# breakout_proto.net
KiCad netlist of a schematic drawn in EAGLE
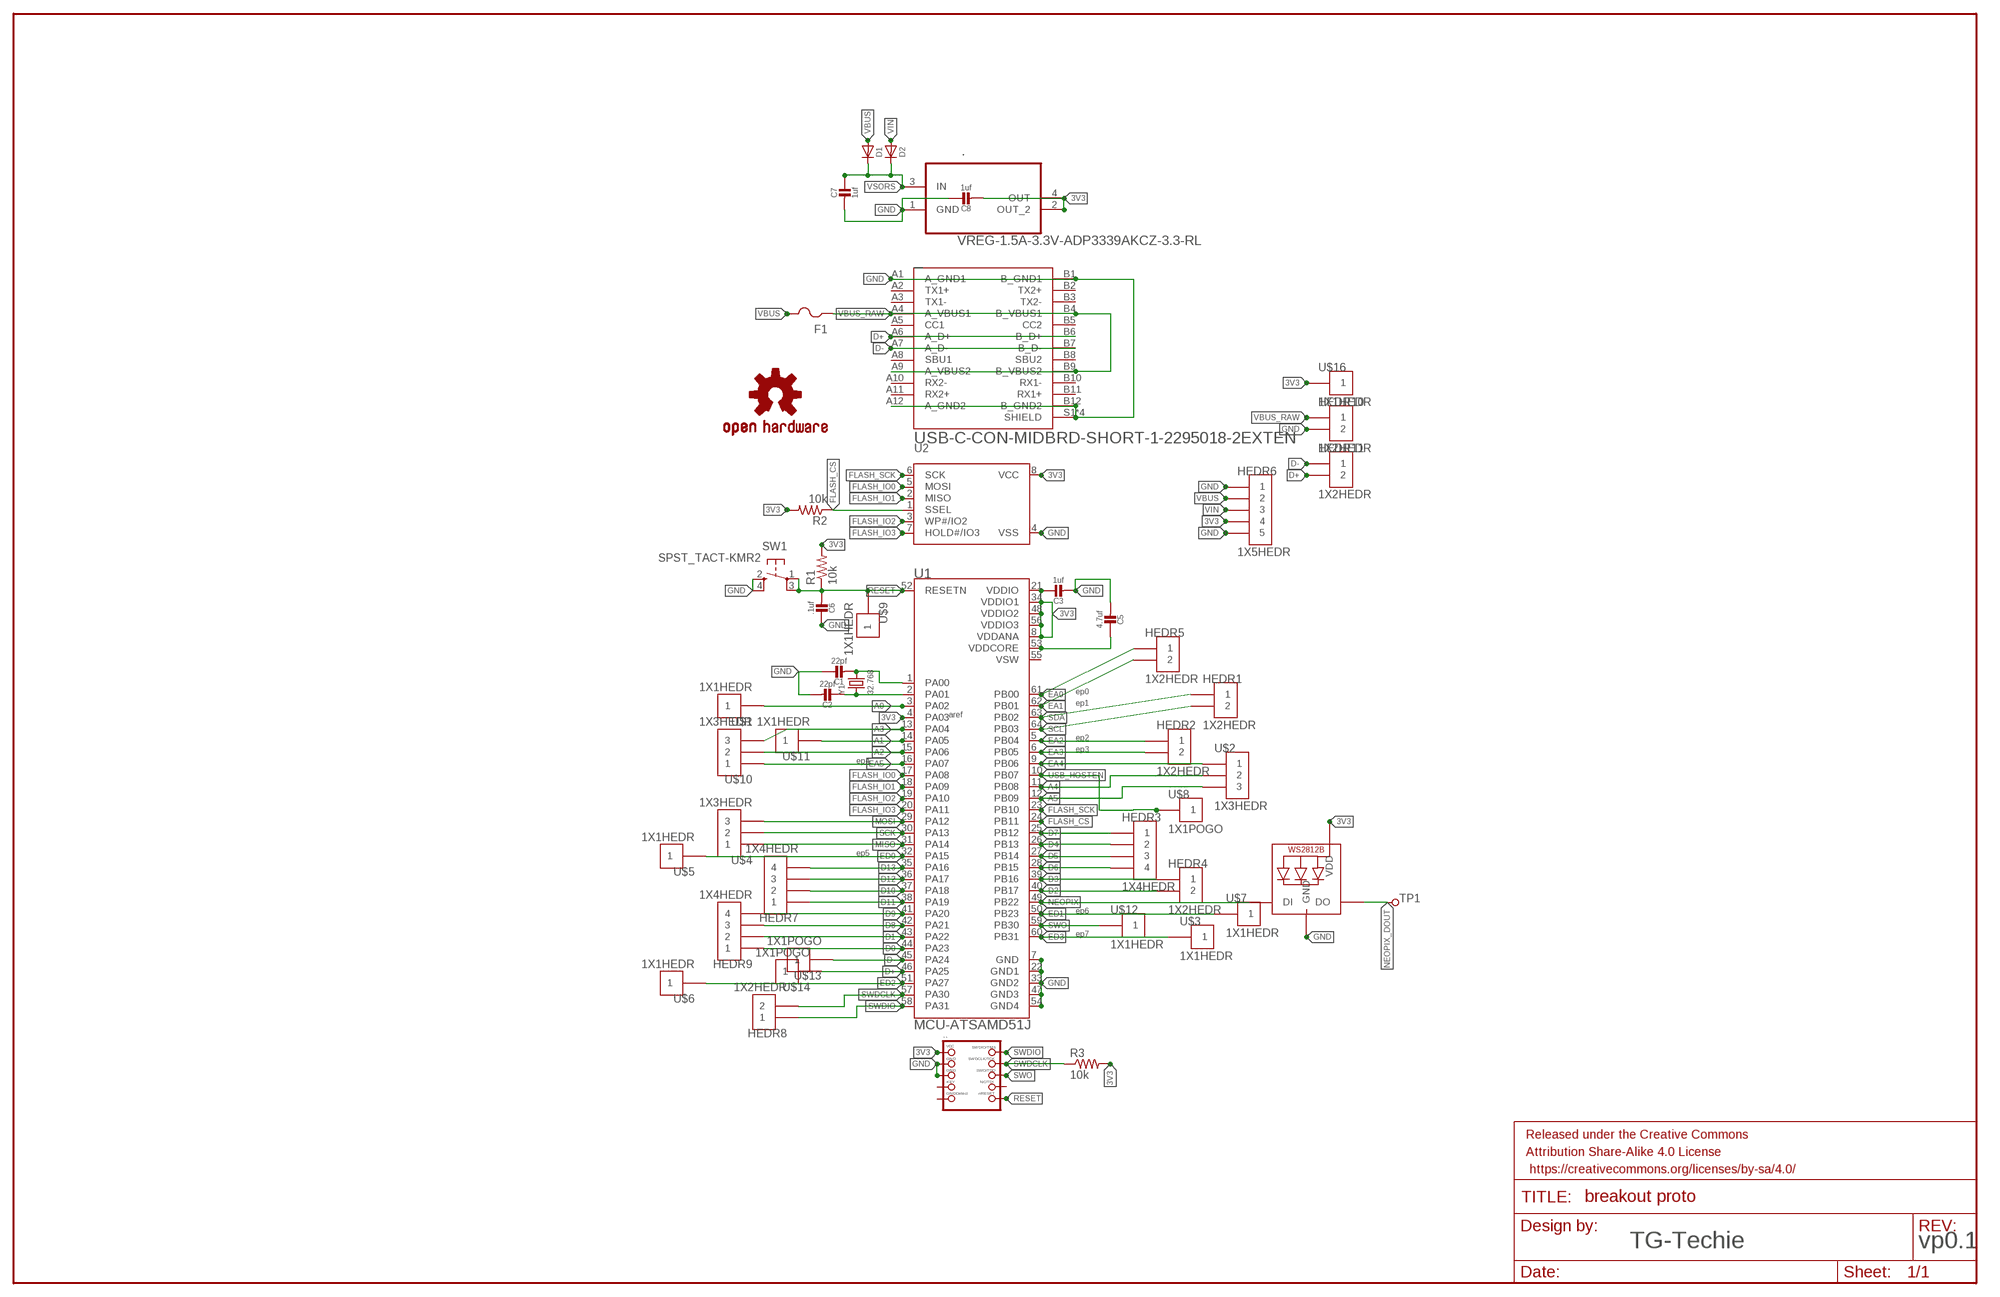
[diagram p0: schematic, sheet 1]

(export (version "E")
  (design (tool "Eeschema 10.0.6"))
  (components
    (comp (ref ".")
      (value "VREG-1.5A-3.3V-ADP3339AKCZ-3.3-RL")
      (footprint "eagle-import:SOT230P700X180-4N")
      (fields (field (name "MF") "Analog Devices") (field (name "MP") "ADP3339AKCZ-3.3-RL"))
      (libsource (lib "eagle-import") (part "VREG-1.5A-3.3V-ADP3339AKCZ-3.3-RL"))
    )
    (comp (ref "..")
      (value "INTRFC-JTAG-CORTEXBOXPOSTS")
      (footprint "eagle-import:2X05_1.27MM_BOX_POSTS")
      (libsource (lib "eagle-import") (part "INTRFC-JTAG-CORTEXBOXPOSTS"))
    )
    (comp (ref "C1")
      (value "22pf")
      (footprint "eagle-import:MICROBUILDER__0805")
      (libsource (lib "eagle-import") (part "C-US__0805"))
    )
    (comp (ref "C2")
      (value "22pf")
      (footprint "eagle-import:MICROBUILDER__0805")
      (libsource (lib "eagle-import") (part "C-US__0805"))
    )
    (comp (ref "C3")
      (value "1uf")
      (footprint "eagle-import:MICROBUILDER__0805")
      (libsource (lib "eagle-import") (part "C-US__0805"))
    )
    (comp (ref "C5")
      (value "4.7uf")
      (footprint "eagle-import:MICROBUILDER__0805")
      (libsource (lib "eagle-import") (part "C-US__0805"))
    )
    (comp (ref "C6")
      (value ".1uf")
      (footprint "eagle-import:MICROBUILDER__0805")
      (libsource (lib "eagle-import") (part "C-US__0805"))
    )
    (comp (ref "C7")
      (value "1uf")
      (footprint "eagle-import:MICROBUILDER__0805")
      (libsource (lib "eagle-import") (part "C-US__0805"))
    )
    (comp (ref "C8")
      (value "1uf")
      (footprint "eagle-import:MICROBUILDER__0805")
      (libsource (lib "eagle-import") (part "C-US__0805"))
    )
    (comp (ref "D1")
      (value "DIODESOD-123")
      (footprint "eagle-import:SOD-123")
      (libsource (lib "eagle-import") (part "DIODESOD-123"))
    )
    (comp (ref "D2")
      (value "DIODESOD-123")
      (footprint "eagle-import:SOD-123")
      (libsource (lib "eagle-import") (part "DIODESOD-123"))
    )
    (comp (ref "F1")
      (value "PTCFUSE-1206")
      (footprint "eagle-import:R1206")
      (libsource (lib "eagle-import") (part "PTCFUSE-1206"))
    )
    (comp (ref "FRAME1")
      (value "FRAME-LEDGER")
      (footprint "eagle-import:CREATIVE_COMMONS")
      (libsource (lib "eagle-import") (part "FRAME-LEDGER"))
    )
    (comp (ref "HEDR1")
      (value "1X2HEDR")
      (footprint "eagle-import:1X2_HEDR")
      (libsource (lib "eagle-import") (part "1X2HEDR"))
    )
    (comp (ref "HEDR2")
      (value "1X2HEDR")
      (footprint "eagle-import:1X2_HEDR")
      (libsource (lib "eagle-import") (part "1X2HEDR"))
    )
    (comp (ref "HEDR3")
      (value "1X4HEDR")
      (footprint "eagle-import:1X4_HEDR")
      (libsource (lib "eagle-import") (part "1X4HEDR"))
    )
    (comp (ref "HEDR4")
      (value "1X2HEDR")
      (footprint "eagle-import:1X2_HEDR")
      (libsource (lib "eagle-import") (part "1X2HEDR"))
    )
    (comp (ref "HEDR5")
      (value "1X2HEDR")
      (footprint "eagle-import:1X2_HEDR")
      (libsource (lib "eagle-import") (part "1X2HEDR"))
    )
    (comp (ref "HEDR6")
      (value "1X5HEDR")
      (footprint "eagle-import:1X5_HEDR")
      (libsource (lib "eagle-import") (part "1X5HEDR"))
    )
    (comp (ref "HEDR7")
      (value "1X4HEDR")
      (footprint "eagle-import:1X4_HEDR")
      (libsource (lib "eagle-import") (part "1X4HEDR"))
    )
    (comp (ref "HEDR8")
      (value "1X2HEDR")
      (footprint "eagle-import:1X2_HEDR")
      (libsource (lib "eagle-import") (part "1X2HEDR"))
    )
    (comp (ref "HEDR9")
      (value "1X4HEDR")
      (footprint "eagle-import:1X4_HEDR")
      (libsource (lib "eagle-import") (part "1X4HEDR"))
    )
    (comp (ref "HEDR10")
      (value "1X2HEDR")
      (footprint "eagle-import:1X2_HEDR")
      (libsource (lib "eagle-import") (part "1X2HEDR"))
    )
    (comp (ref "HEDR11")
      (value "1X2HEDR")
      (footprint "eagle-import:1X2_HEDR")
      (libsource (lib "eagle-import") (part "1X2HEDR"))
    )
    (comp (ref "LED1")
      (value "LED-NEO-WS2812B3535")
      (footprint "eagle-import:LED3535")
      (libsource (lib "eagle-import") (part "LED-NEO-WS2812B3535"))
    )
    (comp (ref "LOGO1")
      (value "OSHW-LOGOMINI")
      (footprint "eagle-import:OSHW-LOGO-MINI")
      (libsource (lib "eagle-import") (part "OSHW-LOGOMINI"))
    )
    (comp (ref "R1")
      (value "10k")
      (footprint "eagle-import:R0805")
      (libsource (lib "eagle-import") (part "R-US_R0805"))
    )
    (comp (ref "R2")
      (value "10k")
      (footprint "eagle-import:R0805")
      (libsource (lib "eagle-import") (part "R-US_R0805"))
    )
    (comp (ref "R3")
      (value "10k")
      (footprint "eagle-import:R0805")
      (libsource (lib "eagle-import") (part "R-US_R0805"))
    )
    (comp (ref "SW1")
      (value "SPST_TACT-KMR2")
      (footprint "eagle-import:KMR2")
      (libsource (lib "eagle-import") (part "SPST_TACT-KMR2"))
    )
    (comp (ref "TP1")
      (value "TESTPOINT_1X1")
      (footprint "eagle-import:1X1_POGO")
      (libsource (lib "eagle-import") (part "TESTPOINT_1X1"))
    )
    (comp (ref "U$1")
      (value "1X1HEDR")
      (footprint "eagle-import:1X1_HEDR")
      (libsource (lib "eagle-import") (part "1X1HEDR"))
    )
    (comp (ref "U$2")
      (value "1X3HEDR")
      (footprint "eagle-import:1X3_HEDR")
      (libsource (lib "eagle-import") (part "1X3HEDR"))
    )
    (comp (ref "U$3")
      (value "1X1HEDR")
      (footprint "eagle-import:1X1_HEDR")
      (libsource (lib "eagle-import") (part "1X1HEDR"))
    )
    (comp (ref "U$4")
      (value "1X3HEDR")
      (footprint "eagle-import:1X3_HEDR")
      (libsource (lib "eagle-import") (part "1X3HEDR"))
    )
    (comp (ref "U$5")
      (value "1X1HEDR")
      (footprint "eagle-import:1X1_HEDR")
      (libsource (lib "eagle-import") (part "1X1HEDR"))
    )
    (comp (ref "U$6")
      (value "1X1HEDR")
      (footprint "eagle-import:1X1_HEDR")
      (libsource (lib "eagle-import") (part "1X1HEDR"))
    )
    (comp (ref "U$7")
      (value "1X1HEDR")
      (footprint "eagle-import:1X1_HEDR")
      (libsource (lib "eagle-import") (part "1X1HEDR"))
    )
    (comp (ref "U$8")
      (value "1X1POGO")
      (footprint "eagle-import:1X1_POGO")
      (libsource (lib "eagle-import") (part "1X1POGO"))
    )
    (comp (ref "U$9")
      (value "1X1HEDR")
      (footprint "eagle-import:1X1_HEDR")
      (libsource (lib "eagle-import") (part "1X1HEDR"))
    )
    (comp (ref "U$10")
      (value "1X3HEDR")
      (footprint "eagle-import:1X3_HEDR")
      (libsource (lib "eagle-import") (part "1X3HEDR"))
    )
    (comp (ref "U$11")
      (value "1X1HEDR")
      (footprint "eagle-import:1X1_HEDR")
      (libsource (lib "eagle-import") (part "1X1HEDR"))
    )
    (comp (ref "U$12")
      (value "1X1HEDR")
      (footprint "eagle-import:1X1_HEDR")
      (libsource (lib "eagle-import") (part "1X1HEDR"))
    )
    (comp (ref "U$13")
      (value "1X1POGO")
      (footprint "eagle-import:1X1_POGO")
      (libsource (lib "eagle-import") (part "1X1POGO"))
    )
    (comp (ref "U$14")
      (value "1X1POGO")
      (footprint "eagle-import:1X1_POGO")
      (libsource (lib "eagle-import") (part "1X1POGO"))
    )
    (comp (ref "U$16")
      (value "1X1HEDR")
      (footprint "eagle-import:1X1_HEDR")
      (libsource (lib "eagle-import") (part "1X1HEDR"))
    )
    (comp (ref "U1")
      (value "MCU-ATSAMD51J")
      (footprint "eagle-import:QFP50P1200X1200X120-64N")
      (fields (field (name "MF") "Microchip") (field (name "MP") "ATSAMD51J20A-AU"))
      (libsource (lib "eagle-import") (part "MCU-ATSAMD51J"))
    )
    (comp (ref "U2")
      (value "FLASH-SPI-SOIC8208MIL")
      (footprint "eagle-import:SOIC8_208MIL")
      (libsource (lib "eagle-import") (part "FLASH-SPI-SOIC8208MIL"))
    )
    (comp (ref "Y1")
      (value "32.768")
      (footprint "eagle-import:MICROBUILDER_CRYSTAL_4.9X1.8")
      (libsource (lib "eagle-import") (part "XTAL_ADA4.9X1.8"))
    )
    (comp (ref "_")
      (value "USB-C-CON-MIDBRD-SHORT-1-2295018-2EXTEN")
      (footprint "eagle-import:TE_1-2295018-2_EXTEN")
      (libsource (lib "eagle-import") (part "USB-C-CON-MIDBRD-SHORT-1-2295018-2EXTEN"))
    )
  )
  (nets
    (net (code "1") (name "/VSW") (class "Default")
      (node (ref "U1") (pin "55") (pinfunction "VSW_55") (pintype "power_in"))
    )
    (net (code "2") (name "3V3") (class "Default")
      (node (ref ".") (pin "2") (pinfunction "OUT_2_2") (pintype "output"))
      (node (ref ".") (pin "4") (pinfunction "OUT_4") (pintype "output"))
      (node (ref "..") (pin "1") (pinfunction "VCC_1") (pintype "power_in"))
      (node (ref "C3") (pin "1") (pinfunction "1_1") (pintype "passive"))
      (node (ref "C8") (pin "2") (pinfunction "2_2") (pintype "passive"))
      (node (ref "HEDR6") (pin "4") (pinfunction "4_4") (pintype "bidirectional"))
      (node (ref "LED1") (pin "2") (pinfunction "VDD_2") (pintype "power_in"))
      (node (ref "R1") (pin "2") (pinfunction "2_2") (pintype "passive"))
      (node (ref "R2") (pin "2") (pinfunction "2_2") (pintype "passive"))
      (node (ref "R3") (pin "2") (pinfunction "2_2") (pintype "passive"))
      (node (ref "U$16") (pin "1") (pinfunction "1_1") (pintype "bidirectional"))
      (node (ref "U1") (pin "21") (pinfunction "VDDIO_21") (pintype "power_in"))
      (node (ref "U1") (pin "34") (pinfunction "VDDIO1_34") (pintype "power_in"))
      (node (ref "U1") (pin "4") (pinfunction "PA03_4") (pintype "bidirectional"))
      (node (ref "U1") (pin "48") (pinfunction "VDDIO2_48") (pintype "power_in"))
      (node (ref "U1") (pin "56") (pinfunction "VDDIO3_56") (pintype "power_in"))
      (node (ref "U1") (pin "8") (pinfunction "VDDANA_8") (pintype "power_in"))
      (node (ref "U2") (pin "8") (pinfunction "VCC_8") (pintype "bidirectional"))
    )
    (net (code "3") (name "A0") (class "Default")
      (node (ref "U$1") (pin "1") (pinfunction "1_1") (pintype "bidirectional"))
      (node (ref "U1") (pin "3") (pinfunction "PA02_3") (pintype "bidirectional"))
    )
    (net (code "4") (name "A1") (class "Default")
      (node (ref "U$11") (pin "1") (pinfunction "1_1") (pintype "bidirectional"))
      (node (ref "U1") (pin "14") (pinfunction "PA05_14") (pintype "bidirectional"))
    )
    (net (code "5") (name "A2") (class "Default")
      (node (ref "U$10") (pin "2") (pinfunction "2_2") (pintype "bidirectional"))
      (node (ref "U1") (pin "15") (pinfunction "PA06_15") (pintype "bidirectional"))
    )
    (net (code "6") (name "A3") (class "Default")
      (node (ref "U$10") (pin "3") (pinfunction "3_3") (pintype "bidirectional"))
      (node (ref "U1") (pin "13") (pinfunction "PA04_13") (pintype "bidirectional"))
    )
    (net (code "7") (name "A4") (class "Default")
      (node (ref "U$2") (pin "2") (pinfunction "2_2") (pintype "bidirectional"))
      (node (ref "U1") (pin "11") (pinfunction "PB08_11") (pintype "bidirectional"))
    )
    (net (code "8") (name "A5") (class "Default")
      (node (ref "U$2") (pin "3") (pinfunction "3_3") (pintype "bidirectional"))
      (node (ref "U1") (pin "12") (pinfunction "PB09_12") (pintype "bidirectional"))
    )
    (net (code "9") (name "D+") (class "Default")
      (node (ref "HEDR11") (pin "2") (pinfunction "2_2") (pintype "bidirectional"))
      (node (ref "U$14") (pin "1") (pinfunction "1_1") (pintype "bidirectional"))
      (node (ref "U1") (pin "46") (pinfunction "PA25_46") (pintype "bidirectional"))
      (node (ref "_") (pin "A6") (pinfunction "A_D+_A6") (pintype "passive"))
      (node (ref "_") (pin "B6") (pinfunction "B_D+_B6") (pintype "passive"))
    )
    (net (code "10") (name "D-") (class "Default")
      (node (ref "HEDR11") (pin "1") (pinfunction "1_1") (pintype "bidirectional"))
      (node (ref "U$13") (pin "1") (pinfunction "1_1") (pintype "bidirectional"))
      (node (ref "U1") (pin "45") (pinfunction "PA24_45") (pintype "bidirectional"))
      (node (ref "_") (pin "A7") (pinfunction "A_D-_A7") (pintype "passive"))
      (node (ref "_") (pin "B7") (pinfunction "B_D-_B7") (pintype "passive"))
    )
    (net (code "11") (name "D0") (class "Default")
      (node (ref "HEDR9") (pin "1") (pinfunction "1_1") (pintype "bidirectional"))
      (node (ref "U1") (pin "44") (pinfunction "PA23_44") (pintype "bidirectional"))
    )
    (net (code "12") (name "D1") (class "Default")
      (node (ref "HEDR9") (pin "2") (pinfunction "2_2") (pintype "bidirectional"))
      (node (ref "U1") (pin "43") (pinfunction "PA22_43") (pintype "bidirectional"))
    )
    (net (code "13") (name "D2") (class "Default")
      (node (ref "HEDR4") (pin "2") (pinfunction "2_2") (pintype "bidirectional"))
      (node (ref "U1") (pin "40") (pinfunction "PB17_40") (pintype "bidirectional"))
    )
    (net (code "14") (name "D3") (class "Default")
      (node (ref "HEDR4") (pin "1") (pinfunction "1_1") (pintype "bidirectional"))
      (node (ref "U1") (pin "39") (pinfunction "PB16_39") (pintype "bidirectional"))
    )
    (net (code "15") (name "D4") (class "Default")
      (node (ref "HEDR3") (pin "2") (pinfunction "2_2") (pintype "bidirectional"))
      (node (ref "U1") (pin "26") (pinfunction "PB13_26") (pintype "bidirectional"))
    )
    (net (code "16") (name "D5") (class "Default")
      (node (ref "HEDR3") (pin "3") (pinfunction "3_3") (pintype "bidirectional"))
      (node (ref "U1") (pin "27") (pinfunction "PB14_27") (pintype "bidirectional"))
    )
    (net (code "17") (name "D6") (class "Default")
      (node (ref "HEDR3") (pin "4") (pinfunction "4_4") (pintype "bidirectional"))
      (node (ref "U1") (pin "28") (pinfunction "PB15_28") (pintype "bidirectional"))
    )
    (net (code "18") (name "D7") (class "Default")
      (node (ref "HEDR3") (pin "1") (pinfunction "1_1") (pintype "bidirectional"))
      (node (ref "U1") (pin "25") (pinfunction "PB12_25") (pintype "bidirectional"))
    )
    (net (code "19") (name "D8") (class "Default")
      (node (ref "HEDR9") (pin "3") (pinfunction "3_3") (pintype "bidirectional"))
      (node (ref "U1") (pin "42") (pinfunction "PA21_42") (pintype "bidirectional"))
    )
    (net (code "20") (name "D9") (class "Default")
      (node (ref "HEDR9") (pin "4") (pinfunction "4_4") (pintype "bidirectional"))
      (node (ref "U1") (pin "41") (pinfunction "PA20_41") (pintype "bidirectional"))
    )
    (net (code "21") (name "D10") (class "Default")
      (node (ref "HEDR7") (pin "2") (pinfunction "2_2") (pintype "bidirectional"))
      (node (ref "U1") (pin "37") (pinfunction "PA18_37") (pintype "bidirectional"))
    )
    (net (code "22") (name "D11") (class "Default")
      (node (ref "HEDR7") (pin "1") (pinfunction "1_1") (pintype "bidirectional"))
      (node (ref "U1") (pin "38") (pinfunction "PA19_38") (pintype "bidirectional"))
    )
    (net (code "23") (name "D12") (class "Default")
      (node (ref "HEDR7") (pin "3") (pinfunction "3_3") (pintype "bidirectional"))
      (node (ref "U1") (pin "36") (pinfunction "PA17_36") (pintype "bidirectional"))
    )
    (net (code "24") (name "D13") (class "Default")
      (node (ref "HEDR7") (pin "4") (pinfunction "4_4") (pintype "bidirectional"))
      (node (ref "U1") (pin "35") (pinfunction "PA16_35") (pintype "bidirectional"))
    )
    (net (code "25") (name "EA0") (class "Default")
      (node (ref "HEDR5") (pin "1") (pinfunction "1_1") (pintype "bidirectional"))
      (node (ref "U1") (pin "61") (pinfunction "PB00_61") (pintype "bidirectional"))
    )
    (net (code "26") (name "EA1") (class "Default")
      (node (ref "HEDR5") (pin "2") (pinfunction "2_2") (pintype "bidirectional"))
      (node (ref "U1") (pin "62") (pinfunction "PB01_62") (pintype "bidirectional"))
    )
    (net (code "27") (name "EA2") (class "Default")
      (node (ref "HEDR2") (pin "1") (pinfunction "1_1") (pintype "bidirectional"))
      (node (ref "U1") (pin "5") (pinfunction "PB04_5") (pintype "bidirectional"))
    )
    (net (code "28") (name "EA3") (class "Default")
      (node (ref "HEDR2") (pin "2") (pinfunction "2_2") (pintype "bidirectional"))
      (node (ref "U1") (pin "6") (pinfunction "PB05_6") (pintype "bidirectional"))
    )
    (net (code "29") (name "EA4") (class "Default")
      (node (ref "U$2") (pin "1") (pinfunction "1_1") (pintype "bidirectional"))
      (node (ref "U1") (pin "9") (pinfunction "PB06_9") (pintype "bidirectional"))
    )
    (net (code "30") (name "EA5") (class "Default")
      (node (ref "U$10") (pin "1") (pinfunction "1_1") (pintype "bidirectional"))
      (node (ref "U1") (pin "16") (pinfunction "PA07_16") (pintype "bidirectional"))
    )
    (net (code "31") (name "ED0") (class "Default")
      (node (ref "U$5") (pin "1") (pinfunction "1_1") (pintype "bidirectional"))
      (node (ref "U1") (pin "32") (pinfunction "PA15_32") (pintype "bidirectional"))
    )
    (net (code "32") (name "ED1") (class "Default")
      (node (ref "U$7") (pin "1") (pinfunction "1_1") (pintype "bidirectional"))
      (node (ref "U1") (pin "50") (pinfunction "PB23_50") (pintype "bidirectional"))
    )
    (net (code "33") (name "ED2") (class "Default")
      (node (ref "U$6") (pin "1") (pinfunction "1_1") (pintype "bidirectional"))
      (node (ref "U1") (pin "51") (pinfunction "PA27_51") (pintype "bidirectional"))
    )
    (net (code "34") (name "ED3") (class "Default")
      (node (ref "U$3") (pin "1") (pinfunction "1_1") (pintype "bidirectional"))
      (node (ref "U1") (pin "60") (pinfunction "PB31_60") (pintype "bidirectional"))
    )
    (net (code "35") (name "FLASH_CS") (class "Default")
      (node (ref "R2") (pin "1") (pinfunction "1_1") (pintype "passive"))
      (node (ref "U1") (pin "24") (pinfunction "PB11_24") (pintype "bidirectional"))
      (node (ref "U2") (pin "1") (pinfunction "SSEL_1") (pintype "bidirectional"))
    )
    (net (code "36") (name "FLASH_IO0") (class "Default")
      (node (ref "U1") (pin "17") (pinfunction "PA08_17") (pintype "bidirectional"))
      (node (ref "U2") (pin "5") (pinfunction "MOSI_5") (pintype "bidirectional"))
    )
    (net (code "37") (name "FLASH_IO1") (class "Default")
      (node (ref "U1") (pin "18") (pinfunction "PA09_18") (pintype "bidirectional"))
      (node (ref "U2") (pin "2") (pinfunction "MISO_2") (pintype "bidirectional"))
    )
    (net (code "38") (name "FLASH_IO2") (class "Default")
      (node (ref "U1") (pin "19") (pinfunction "PA10_19") (pintype "bidirectional"))
      (node (ref "U2") (pin "3") (pinfunction "WP#/IO2_3") (pintype "bidirectional"))
    )
    (net (code "39") (name "FLASH_IO3") (class "Default")
      (node (ref "U1") (pin "20") (pinfunction "PA11_20") (pintype "bidirectional"))
      (node (ref "U2") (pin "7") (pinfunction "HOLD#/IO3_7") (pintype "bidirectional"))
    )
    (net (code "40") (name "FLASH_SCK") (class "Default")
      (node (ref "U1") (pin "23") (pinfunction "PB10_23") (pintype "bidirectional"))
      (node (ref "U2") (pin "6") (pinfunction "SCK_6") (pintype "bidirectional"))
    )
    (net (code "41") (name "GND") (class "Default")
      (node (ref ".") (pin "1") (pinfunction "GND_1") (pintype "passive"))
      (node (ref "..") (pin "3") (pinfunction "GND_3") (pintype "power_in"))
      (node (ref "..") (pin "5") (pinfunction "GND_5") (pintype "power_in"))
      (node (ref "C1") (pin "1") (pinfunction "1_1") (pintype "passive"))
      (node (ref "C2") (pin "2") (pinfunction "2_2") (pintype "passive"))
      (node (ref "C3") (pin "2") (pinfunction "2_2") (pintype "passive"))
      (node (ref "C5") (pin "2") (pinfunction "2_2") (pintype "passive"))
      (node (ref "C6") (pin "1") (pinfunction "1_1") (pintype "passive"))
      (node (ref "C7") (pin "2") (pinfunction "2_2") (pintype "passive"))
      (node (ref "C8") (pin "1") (pinfunction "1_1") (pintype "passive"))
      (node (ref "HEDR10") (pin "2") (pinfunction "2_2") (pintype "bidirectional"))
      (node (ref "HEDR6") (pin "1") (pinfunction "1_1") (pintype "bidirectional"))
      (node (ref "HEDR6") (pin "5") (pinfunction "5_5") (pintype "bidirectional"))
      (node (ref "LED1") (pin "4") (pinfunction "GND_4") (pintype "power_in"))
      (node (ref "SW1") (pin "2") (pinfunction "S_2") (pintype "passive"))
      (node (ref "SW1") (pin "4") (pinfunction "S1_4") (pintype "passive"))
      (node (ref "U1") (pin "22") (pinfunction "GND1_22") (pintype "power_in"))
      (node (ref "U1") (pin "33") (pinfunction "GND2_33") (pintype "power_in"))
      (node (ref "U1") (pin "47") (pinfunction "GND3_47") (pintype "power_in"))
      (node (ref "U1") (pin "54") (pinfunction "GND4_54") (pintype "power_in"))
      (node (ref "U1") (pin "7") (pinfunction "GND_7") (pintype "power_in"))
      (node (ref "U2") (pin "4") (pinfunction "VSS_4") (pintype "bidirectional"))
      (node (ref "_") (pin "A1") (pinfunction "A_GND1_A1") (pintype "passive"))
      (node (ref "_") (pin "A12") (pinfunction "A_GND2_A12") (pintype "passive"))
      (node (ref "_") (pin "B1") (pinfunction "B_GND1_B1") (pintype "passive"))
      (node (ref "_") (pin "B12") (pinfunction "B_GND2_B12") (pintype "passive"))
      (node (ref "_") (pin "S1") (pinfunction "SHIELD_S1") (pintype "passive"))
      (node (ref "_") (pin "S2") (pinfunction "SHIELD_S2") (pintype "passive"))
      (node (ref "_") (pin "S3") (pinfunction "SHIELD_S3") (pintype "passive"))
      (node (ref "_") (pin "S4") (pinfunction "SHIELD_S4") (pintype "passive"))
    )
    (net (code "42") (name "MISO") (class "Default")
      (node (ref "U$4") (pin "1") (pinfunction "1_1") (pintype "bidirectional"))
      (node (ref "U1") (pin "31") (pinfunction "PA14_31") (pintype "bidirectional"))
    )
    (net (code "43") (name "MOSI") (class "Default")
      (node (ref "U$4") (pin "3") (pinfunction "3_3") (pintype "bidirectional"))
      (node (ref "U1") (pin "29") (pinfunction "PA12_29") (pintype "bidirectional"))
    )
    (net (code "44") (name "NEOPIX") (class "Default")
      (node (ref "LED1") (pin "1") (pinfunction "DI_1") (pintype "input"))
      (node (ref "U1") (pin "49") (pinfunction "PB22_49") (pintype "bidirectional"))
    )
    (net (code "45") (name "NEOPIX_DOUT") (class "Default")
      (node (ref "LED1") (pin "3") (pinfunction "DO_3") (pintype "output"))
      (node (ref "TP1") (pin "1") (pinfunction "P1_1") (pintype "bidirectional"))
    )
    (net (code "46") (name "Net-(U1-PA00)") (class "Default")
      (node (ref "C1") (pin "2") (pinfunction "2_2") (pintype "passive"))
      (node (ref "U1") (pin "1") (pinfunction "PA00_1") (pintype "bidirectional"))
      (node (ref "Y1") (pin "2") (pinfunction "2_2") (pintype "passive"))
    )
    (net (code "47") (name "Net-(U1-PA01)") (class "Default")
      (node (ref "C2") (pin "1") (pinfunction "1_1") (pintype "passive"))
      (node (ref "U1") (pin "2") (pinfunction "PA01_2") (pintype "bidirectional"))
      (node (ref "Y1") (pin "1") (pinfunction "1_1") (pintype "passive"))
    )
    (net (code "48") (name "Net-(U1-VDDCORE)") (class "Default")
      (node (ref "C5") (pin "1") (pinfunction "1_1") (pintype "passive"))
      (node (ref "U1") (pin "53") (pinfunction "VDDCORE_53") (pintype "power_in"))
    )
    (net (code "49") (name "RESET") (class "Default")
      (node (ref "..") (pin "10") (pinfunction "NRESET_10") (pintype "bidirectional"))
      (node (ref "C6") (pin "2") (pinfunction "2_2") (pintype "passive"))
      (node (ref "R1") (pin "1") (pinfunction "1_1") (pintype "passive"))
      (node (ref "SW1") (pin "1") (pinfunction "P_1") (pintype "passive"))
      (node (ref "SW1") (pin "3") (pinfunction "P1_3") (pintype "passive"))
      (node (ref "U$9") (pin "1") (pinfunction "1_1") (pintype "bidirectional"))
      (node (ref "U1") (pin "52") (pinfunction "RESETN_52") (pintype "input"))
    )
    (net (code "50") (name "SCK") (class "Default")
      (node (ref "U$4") (pin "2") (pinfunction "2_2") (pintype "bidirectional"))
      (node (ref "U1") (pin "30") (pinfunction "PA13_30") (pintype "bidirectional"))
    )
    (net (code "51") (name "SCL") (class "Default")
      (node (ref "HEDR1") (pin "2") (pinfunction "2_2") (pintype "bidirectional"))
      (node (ref "U1") (pin "64") (pinfunction "PB03_64") (pintype "bidirectional"))
    )
    (net (code "52") (name "SDA") (class "Default")
      (node (ref "HEDR1") (pin "1") (pinfunction "1_1") (pintype "bidirectional"))
      (node (ref "U1") (pin "63") (pinfunction "PB02_63") (pintype "bidirectional"))
    )
    (net (code "53") (name "SWDCLK") (class "Default")
      (node (ref "..") (pin "4") (pinfunction "SWDCLK_4") (pintype "bidirectional"))
      (node (ref "HEDR8") (pin "2") (pinfunction "2_2") (pintype "bidirectional"))
      (node (ref "R3") (pin "1") (pinfunction "1_1") (pintype "passive"))
      (node (ref "U1") (pin "57") (pinfunction "PA30_57") (pintype "bidirectional"))
    )
    (net (code "54") (name "SWDIO") (class "Default")
      (node (ref "..") (pin "2") (pinfunction "SWDIO_2") (pintype "bidirectional"))
      (node (ref "HEDR8") (pin "1") (pinfunction "1_1") (pintype "bidirectional"))
      (node (ref "U1") (pin "58") (pinfunction "PA31_58") (pintype "bidirectional"))
    )
    (net (code "55") (name "SWO") (class "Default")
      (node (ref "..") (pin "6") (pinfunction "SWO_6") (pintype "bidirectional"))
      (node (ref "U$12") (pin "1") (pinfunction "1_1") (pintype "bidirectional"))
      (node (ref "U1") (pin "59") (pinfunction "PB30_59") (pintype "bidirectional"))
    )
    (net (code "56") (name "USB_HOSTEN") (class "Default")
      (node (ref "U$8") (pin "1") (pinfunction "1_1") (pintype "bidirectional"))
      (node (ref "U1") (pin "10") (pinfunction "PB07_10") (pintype "bidirectional"))
    )
    (net (code "57") (name "VBUS") (class "Default")
      (node (ref "D1") (pin "A") (pinfunction "A_A") (pintype "passive"))
      (node (ref "F1") (pin "2") (pinfunction "2_2") (pintype "passive"))
      (node (ref "HEDR6") (pin "2") (pinfunction "2_2") (pintype "bidirectional"))
    )
    (net (code "58") (name "VBUS_RAW") (class "Default")
      (node (ref "F1") (pin "1") (pinfunction "1_1") (pintype "passive"))
      (node (ref "HEDR10") (pin "1") (pinfunction "1_1") (pintype "bidirectional"))
      (node (ref "_") (pin "A4") (pinfunction "A_VBUS1_A4") (pintype "passive"))
      (node (ref "_") (pin "A9") (pinfunction "A_VBUS2_A9") (pintype "passive"))
      (node (ref "_") (pin "B4") (pinfunction "B_VBUS1_B4") (pintype "passive"))
      (node (ref "_") (pin "B9") (pinfunction "B_VBUS2_B9") (pintype "passive"))
    )
    (net (code "59") (name "VIN") (class "Default")
      (node (ref "D2") (pin "A") (pinfunction "A_A") (pintype "passive"))
      (node (ref "HEDR6") (pin "3") (pinfunction "3_3") (pintype "bidirectional"))
    )
    (net (code "60") (name "VSORS") (class "Default")
      (node (ref ".") (pin "3") (pinfunction "IN_3") (pintype "input"))
      (node (ref "C7") (pin "1") (pinfunction "1_1") (pintype "passive"))
      (node (ref "D1") (pin "C") (pinfunction "C_C") (pintype "passive"))
      (node (ref "D2") (pin "C") (pinfunction "C_C") (pintype "passive"))
    )
    (net (code "61") (name "unconnected-(..-GNDDETECT-Pad9)") (class "Default")
      (node (ref "..") (pin "9") (pinfunction "GNDDETECT_9") (pintype "bidirectional"))
    )
    (net (code "62") (name "unconnected-(..-KEY-Pad7)") (class "Default")
      (node (ref "..") (pin "7") (pinfunction "KEY_7") (pintype "bidirectional"))
    )
    (net (code "63") (name "unconnected-(..-TDI-Pad8)") (class "Default")
      (node (ref "..") (pin "8") (pinfunction "TDI_8") (pintype "bidirectional"))
    )
    (net (code "64") (name "unconnected-(_-CC1-PadA5)") (class "Default")
      (node (ref "_") (pin "A5") (pinfunction "CC1_A5") (pintype "passive"))
    )
    (net (code "65") (name "unconnected-(_-CC2-PadB5)") (class "Default")
      (node (ref "_") (pin "B5") (pinfunction "CC2_B5") (pintype "passive"))
    )
    (net (code "66") (name "unconnected-(_-RX1+-PadB11)") (class "Default")
      (node (ref "_") (pin "B11") (pinfunction "RX1+_B11") (pintype "passive"))
    )
    (net (code "67") (name "unconnected-(_-RX1--PadB10)") (class "Default")
      (node (ref "_") (pin "B10") (pinfunction "RX1-_B10") (pintype "passive"))
    )
    (net (code "68") (name "unconnected-(_-RX2+-PadA11)") (class "Default")
      (node (ref "_") (pin "A11") (pinfunction "RX2+_A11") (pintype "passive"))
    )
    (net (code "69") (name "unconnected-(_-RX2--PadA10)") (class "Default")
      (node (ref "_") (pin "A10") (pinfunction "RX2-_A10") (pintype "passive"))
    )
    (net (code "70") (name "unconnected-(_-SBU1-PadA8)") (class "Default")
      (node (ref "_") (pin "A8") (pinfunction "SBU1_A8") (pintype "passive"))
    )
    (net (code "71") (name "unconnected-(_-SBU2-PadB8)") (class "Default")
      (node (ref "_") (pin "B8") (pinfunction "SBU2_B8") (pintype "passive"))
    )
    (net (code "72") (name "unconnected-(_-TX1+-PadA2)") (class "Default")
      (node (ref "_") (pin "A2") (pinfunction "TX1+_A2") (pintype "passive"))
    )
    (net (code "73") (name "unconnected-(_-TX1--PadA3)") (class "Default")
      (node (ref "_") (pin "A3") (pinfunction "TX1-_A3") (pintype "passive"))
    )
    (net (code "74") (name "unconnected-(_-TX2+-PadB2)") (class "Default")
      (node (ref "_") (pin "B2") (pinfunction "TX2+_B2") (pintype "passive"))
    )
    (net (code "75") (name "unconnected-(_-TX2--PadB3)") (class "Default")
      (node (ref "_") (pin "B3") (pinfunction "TX2-_B3") (pintype "passive"))
    )
  )
)
